# Sensor.net
KiCad netlist of a schematic drawn in EAGLE
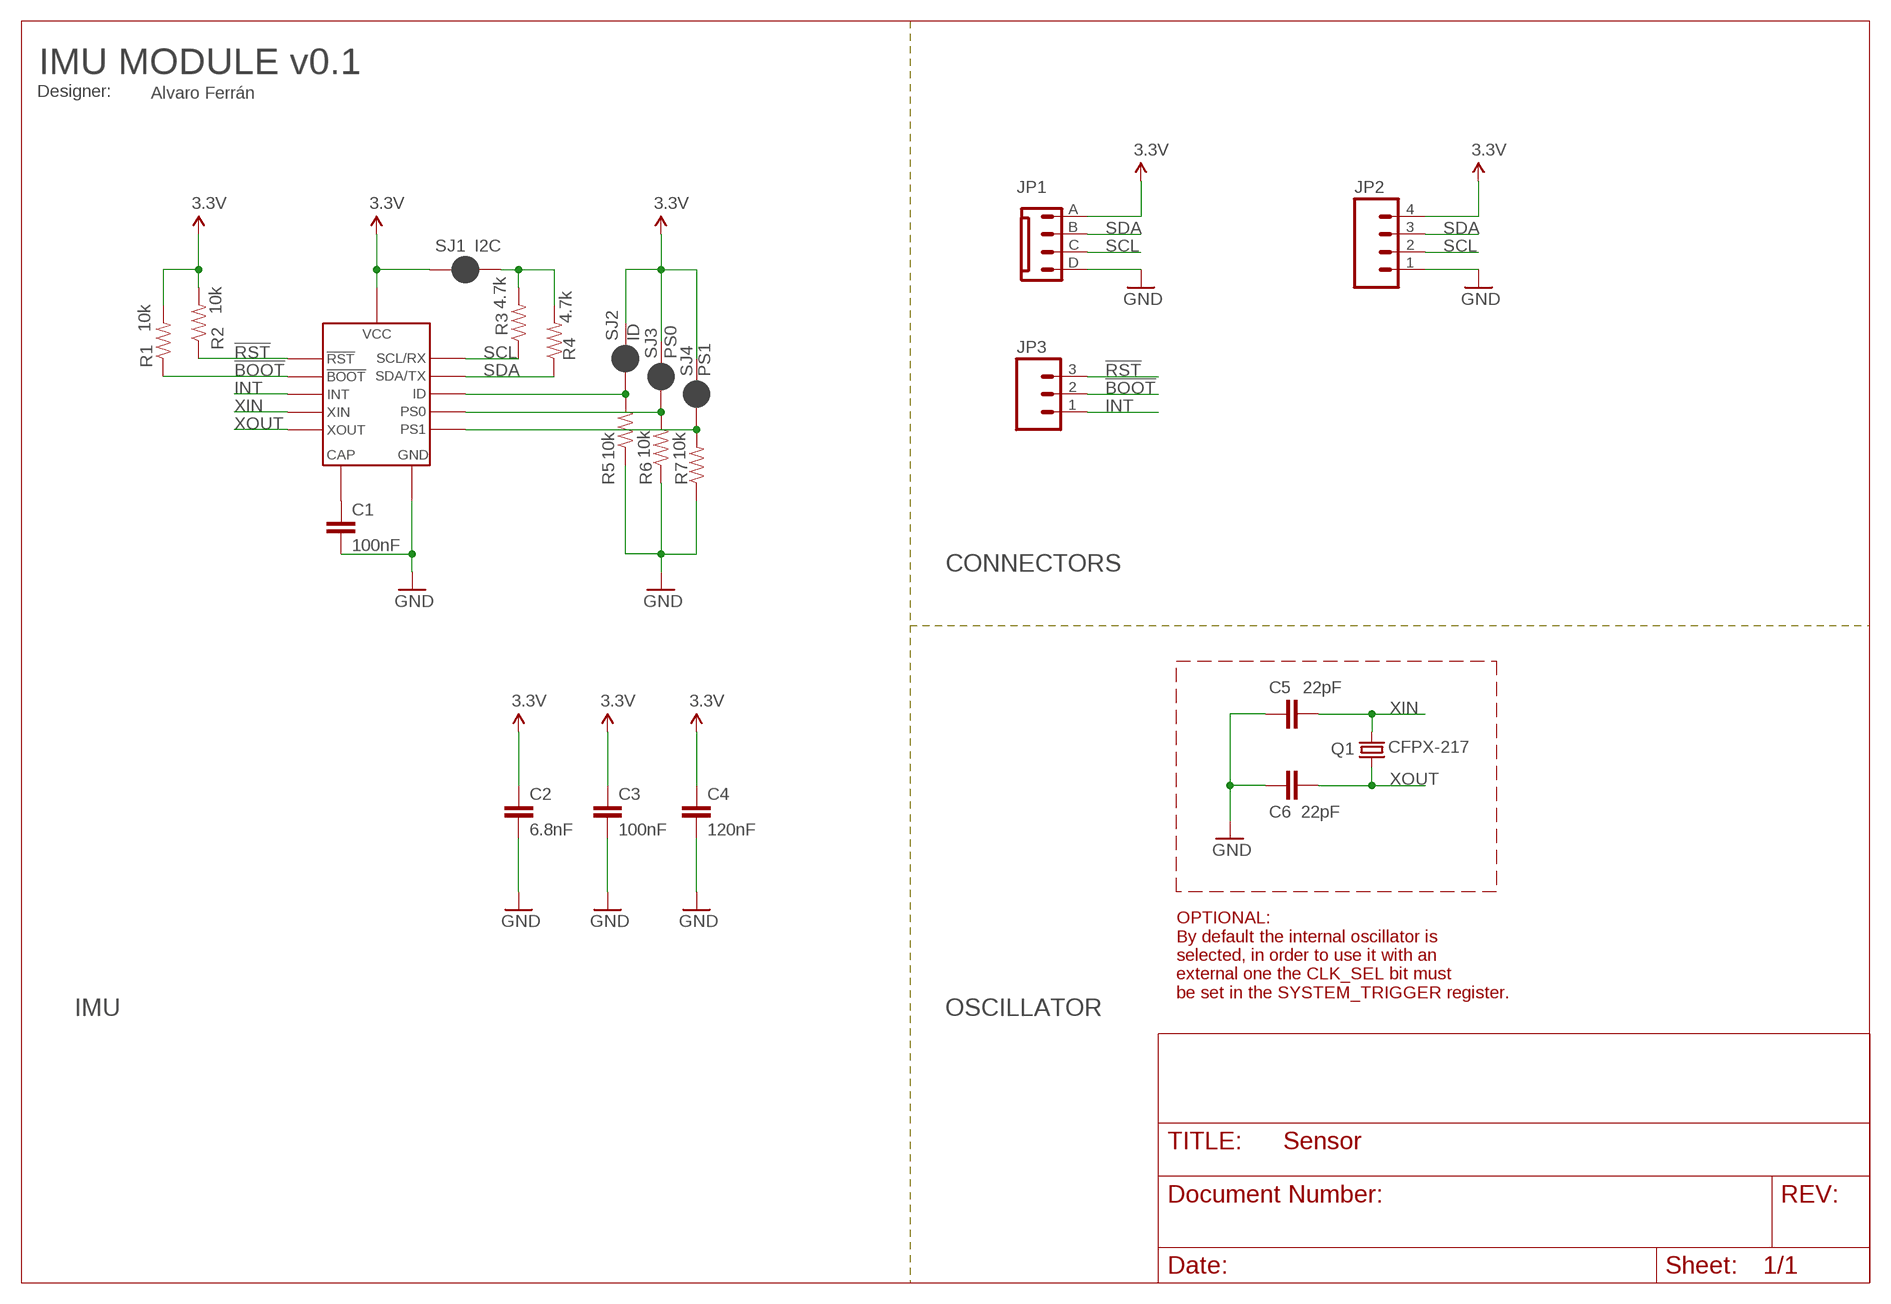
[diagram p0: schematic, sheet 1]

(export (version "E")
  (design (tool "Eeschema 10.0.6"))
  (components
    (comp (ref "C1")
      (value "100nF")
      (footprint "eagle-import:0603-CAP")
      (libsource (lib "eagle-import") (part "CAP0603-CAP"))
    )
    (comp (ref "C2")
      (value "6.8nF")
      (footprint "eagle-import:0603-CAP")
      (libsource (lib "eagle-import") (part "CAP0603-CAP"))
    )
    (comp (ref "C3")
      (value "100nF")
      (footprint "eagle-import:0603-CAP")
      (libsource (lib "eagle-import") (part "CAP0603-CAP"))
    )
    (comp (ref "C4")
      (value "120nF")
      (footprint "eagle-import:0603-CAP")
      (libsource (lib "eagle-import") (part "CAP0603-CAP"))
    )
    (comp (ref "C5")
      (value "22pF")
      (footprint "eagle-import:0402-CAP")
      (libsource (lib "eagle-import") (part "CAP0402-CAP"))
    )
    (comp (ref "C6")
      (value "22pF")
      (footprint "eagle-import:0402-CAP")
      (libsource (lib "eagle-import") (part "CAP0402-CAP"))
    )
    (comp (ref "JP1")
      (value "MX-6410-04A")
      (footprint "eagle-import:MX-6410-04A")
      (libsource (lib "eagle-import") (part "MX-6410-04A"))
    )
    (comp (ref "JP2")
      (value "M04LOCK")
      (footprint "eagle-import:1X04_LOCK")
      (libsource (lib "eagle-import") (part "M04LOCK"))
    )
    (comp (ref "JP3")
      (value "M03LOCK")
      (footprint "eagle-import:1X03_LOCK")
      (libsource (lib "eagle-import") (part "M03LOCK"))
    )
    (comp (ref "Q1")
      (value "CFPX-217")
      (footprint "eagle-import:CFPX-217")
      (libsource (lib "eagle-import") (part "CFPX-217"))
    )
    (comp (ref "R1")
      (value "10k")
      (footprint "eagle-import:0402-RES")
      (libsource (lib "eagle-import") (part "RESISTOR0402-RES"))
    )
    (comp (ref "R2")
      (value "10k")
      (footprint "eagle-import:0402-RES")
      (libsource (lib "eagle-import") (part "RESISTOR0402-RES"))
    )
    (comp (ref "R3")
      (value "4.7k")
      (footprint "eagle-import:0402-RES")
      (libsource (lib "eagle-import") (part "RESISTOR0402-RES"))
    )
    (comp (ref "R4")
      (value "4.7k")
      (footprint "eagle-import:0402-RES")
      (libsource (lib "eagle-import") (part "RESISTOR0402-RES"))
    )
    (comp (ref "R5")
      (value "10k")
      (footprint "eagle-import:0402-RES")
      (libsource (lib "eagle-import") (part "RESISTOR0402-RES"))
    )
    (comp (ref "R6")
      (value "10k")
      (footprint "eagle-import:0402-RES")
      (libsource (lib "eagle-import") (part "RESISTOR0402-RES"))
    )
    (comp (ref "R7")
      (value "10k")
      (footprint "eagle-import:0402-RES")
      (libsource (lib "eagle-import") (part "RESISTOR0402-RES"))
    )
    (comp (ref "SJ1")
      (value "I2C")
      (footprint "eagle-import:PAD-JUMPER-2-NC_BY_PASTE_YES_SILK")
      (libsource (lib "eagle-import") (part "JUMPER-PAD-2-NC_BY_PASTE"))
    )
    (comp (ref "SJ2")
      (value "ID")
      (footprint "eagle-import:PAD-JUMPER-2-NC_BY_PASTE_YES_SILK")
      (libsource (lib "eagle-import") (part "JUMPER-PAD-2-NC_BY_PASTE"))
    )
    (comp (ref "SJ3")
      (value "PS0")
      (footprint "eagle-import:PAD-JUMPER-2-NC_BY_PASTE_YES_SILK")
      (libsource (lib "eagle-import") (part "JUMPER-PAD-2-NC_BY_PASTE"))
    )
    (comp (ref "SJ4")
      (value "PS1")
      (footprint "eagle-import:PAD-JUMPER-2-NC_BY_PASTE_YES_SILK")
      (libsource (lib "eagle-import") (part "JUMPER-PAD-2-NC_BY_PASTE"))
    )
    (comp (ref "U1")
      (value "BNO055")
      (footprint "eagle-import:BNO055")
      (libsource (lib "eagle-import") (part "BNO055"))
    )
  )
  (nets
    (net (code "1") (name "/INT") (class "Default")
      (node (ref "JP3") (pin "1") (pinfunction "1_1") (pintype "passive"))
      (node (ref "U1") (pin "14") (pinfunction "INT_14") (pintype "bidirectional"))
    )
    (net (code "2") (name "/SCL") (class "Default")
      (node (ref "JP1") (pin "C") (pinfunction "C_C") (pintype "passive"))
      (node (ref "JP2") (pin "2") (pinfunction "2_2") (pintype "passive"))
      (node (ref "R3") (pin "1") (pinfunction "1_1") (pintype "passive"))
      (node (ref "U1") (pin "19") (pinfunction "SCL/RX_19") (pintype "bidirectional"))
    )
    (net (code "3") (name "/SDA") (class "Default")
      (node (ref "JP1") (pin "B") (pinfunction "B_B") (pintype "passive"))
      (node (ref "JP2") (pin "3") (pinfunction "3_3") (pintype "passive"))
      (node (ref "R4") (pin "1") (pinfunction "1_1") (pintype "passive"))
      (node (ref "U1") (pin "20") (pinfunction "SDA/TX_20") (pintype "bidirectional"))
    )
    (net (code "4") (name "/XIN") (class "Default")
      (node (ref "C5") (pin "2") (pinfunction "2_2") (pintype "passive"))
      (node (ref "Q1") (pin "2") (pinfunction "2_2") (pintype "passive"))
      (node (ref "U1") (pin "27") (pinfunction "XIN_27") (pintype "bidirectional"))
    )
    (net (code "5") (name "/XOUT") (class "Default")
      (node (ref "C6") (pin "2") (pinfunction "2_2") (pintype "passive"))
      (node (ref "Q1") (pin "1") (pinfunction "1_1") (pintype "passive"))
      (node (ref "U1") (pin "26") (pinfunction "XOUT_26") (pintype "bidirectional"))
    )
    (net (code "6") (name "/~{BOOT}") (class "Default")
      (node (ref "JP3") (pin "2") (pinfunction "2_2") (pintype "passive"))
      (node (ref "R1") (pin "1") (pinfunction "1_1") (pintype "passive"))
      (node (ref "U1") (pin "4") (pinfunction "BOOT_4") (pintype "bidirectional"))
    )
    (net (code "7") (name "/~{RST}") (class "Default")
      (node (ref "JP3") (pin "3") (pinfunction "3_3") (pintype "passive"))
      (node (ref "R2") (pin "1") (pinfunction "1_1") (pintype "passive"))
      (node (ref "U1") (pin "11") (pinfunction "RST_11") (pintype "bidirectional"))
    )
    (net (code "8") (name "3.3V") (class "Default")
      (node (ref "C2") (pin "1") (pinfunction "1_1") (pintype "passive"))
      (node (ref "C3") (pin "1") (pinfunction "1_1") (pintype "passive"))
      (node (ref "C4") (pin "1") (pinfunction "1_1") (pintype "passive"))
      (node (ref "JP1") (pin "A") (pinfunction "A_A") (pintype "passive"))
      (node (ref "JP2") (pin "4") (pinfunction "4_4") (pintype "passive"))
      (node (ref "R1") (pin "2") (pinfunction "2_2") (pintype "passive"))
      (node (ref "R2") (pin "2") (pinfunction "2_2") (pintype "passive"))
      (node (ref "SJ1") (pin "2") (pinfunction "2_2") (pintype "passive"))
      (node (ref "SJ2") (pin "2") (pinfunction "2_2") (pintype "passive"))
      (node (ref "SJ3") (pin "2") (pinfunction "2_2") (pintype "passive"))
      (node (ref "SJ4") (pin "2") (pinfunction "2_2") (pintype "passive"))
      (node (ref "U1") (pin "28") (pinfunction "VCC_28") (pintype "bidirectional"))
      (node (ref "U1") (pin "3") (pinfunction "VCC_3") (pintype "bidirectional"))
    )
    (net (code "9") (name "GND") (class "Default")
      (node (ref "C1") (pin "2") (pinfunction "2_2") (pintype "passive"))
      (node (ref "C2") (pin "2") (pinfunction "2_2") (pintype "passive"))
      (node (ref "C3") (pin "2") (pinfunction "2_2") (pintype "passive"))
      (node (ref "C4") (pin "2") (pinfunction "2_2") (pintype "passive"))
      (node (ref "C5") (pin "1") (pinfunction "1_1") (pintype "passive"))
      (node (ref "C6") (pin "1") (pinfunction "1_1") (pintype "passive"))
      (node (ref "JP1") (pin "D") (pinfunction "D_D") (pintype "passive"))
      (node (ref "JP2") (pin "1") (pinfunction "1_1") (pintype "passive"))
      (node (ref "R5") (pin "1") (pinfunction "1_1") (pintype "passive"))
      (node (ref "R6") (pin "1") (pinfunction "1_1") (pintype "passive"))
      (node (ref "R7") (pin "1") (pinfunction "1_1") (pintype "passive"))
      (node (ref "U1") (pin "10") (pinfunction "GND_10") (pintype "power_in"))
      (node (ref "U1") (pin "15") (pinfunction "GND_15") (pintype "power_in"))
      (node (ref "U1") (pin "16") (pinfunction "GND_16") (pintype "power_in"))
      (node (ref "U1") (pin "18") (pinfunction "GND_18") (pintype "power_in"))
      (node (ref "U1") (pin "2") (pinfunction "GND_2") (pintype "power_in"))
      (node (ref "U1") (pin "25") (pinfunction "GND_25") (pintype "power_in"))
    )
    (net (code "10") (name "Net-(R3-Pad2)") (class "Default")
      (node (ref "R3") (pin "2") (pinfunction "2_2") (pintype "passive"))
      (node (ref "R4") (pin "2") (pinfunction "2_2") (pintype "passive"))
      (node (ref "SJ1") (pin "1") (pinfunction "1_1") (pintype "passive"))
    )
    (net (code "11") (name "Net-(U1-CAP)") (class "Default")
      (node (ref "C1") (pin "1") (pinfunction "1_1") (pintype "passive"))
      (node (ref "U1") (pin "9") (pinfunction "CAP_9") (pintype "bidirectional"))
    )
    (net (code "12") (name "Net-(U1-ID)") (class "Default")
      (node (ref "R5") (pin "2") (pinfunction "2_2") (pintype "passive"))
      (node (ref "SJ2") (pin "1") (pinfunction "1_1") (pintype "passive"))
      (node (ref "U1") (pin "17") (pinfunction "ID_17") (pintype "bidirectional"))
    )
    (net (code "13") (name "Net-(U1-PS0)") (class "Default")
      (node (ref "R6") (pin "2") (pinfunction "2_2") (pintype "passive"))
      (node (ref "SJ3") (pin "1") (pinfunction "1_1") (pintype "passive"))
      (node (ref "U1") (pin "6") (pinfunction "PS0_6") (pintype "bidirectional"))
    )
    (net (code "14") (name "Net-(U1-PS1)") (class "Default")
      (node (ref "R7") (pin "2") (pinfunction "2_2") (pintype "passive"))
      (node (ref "SJ4") (pin "1") (pinfunction "1_1") (pintype "passive"))
      (node (ref "U1") (pin "5") (pinfunction "PS1_5") (pintype "bidirectional"))
    )
  )
)
